# mockup.net
KiCad netlist of a schematic drawn in EAGLE
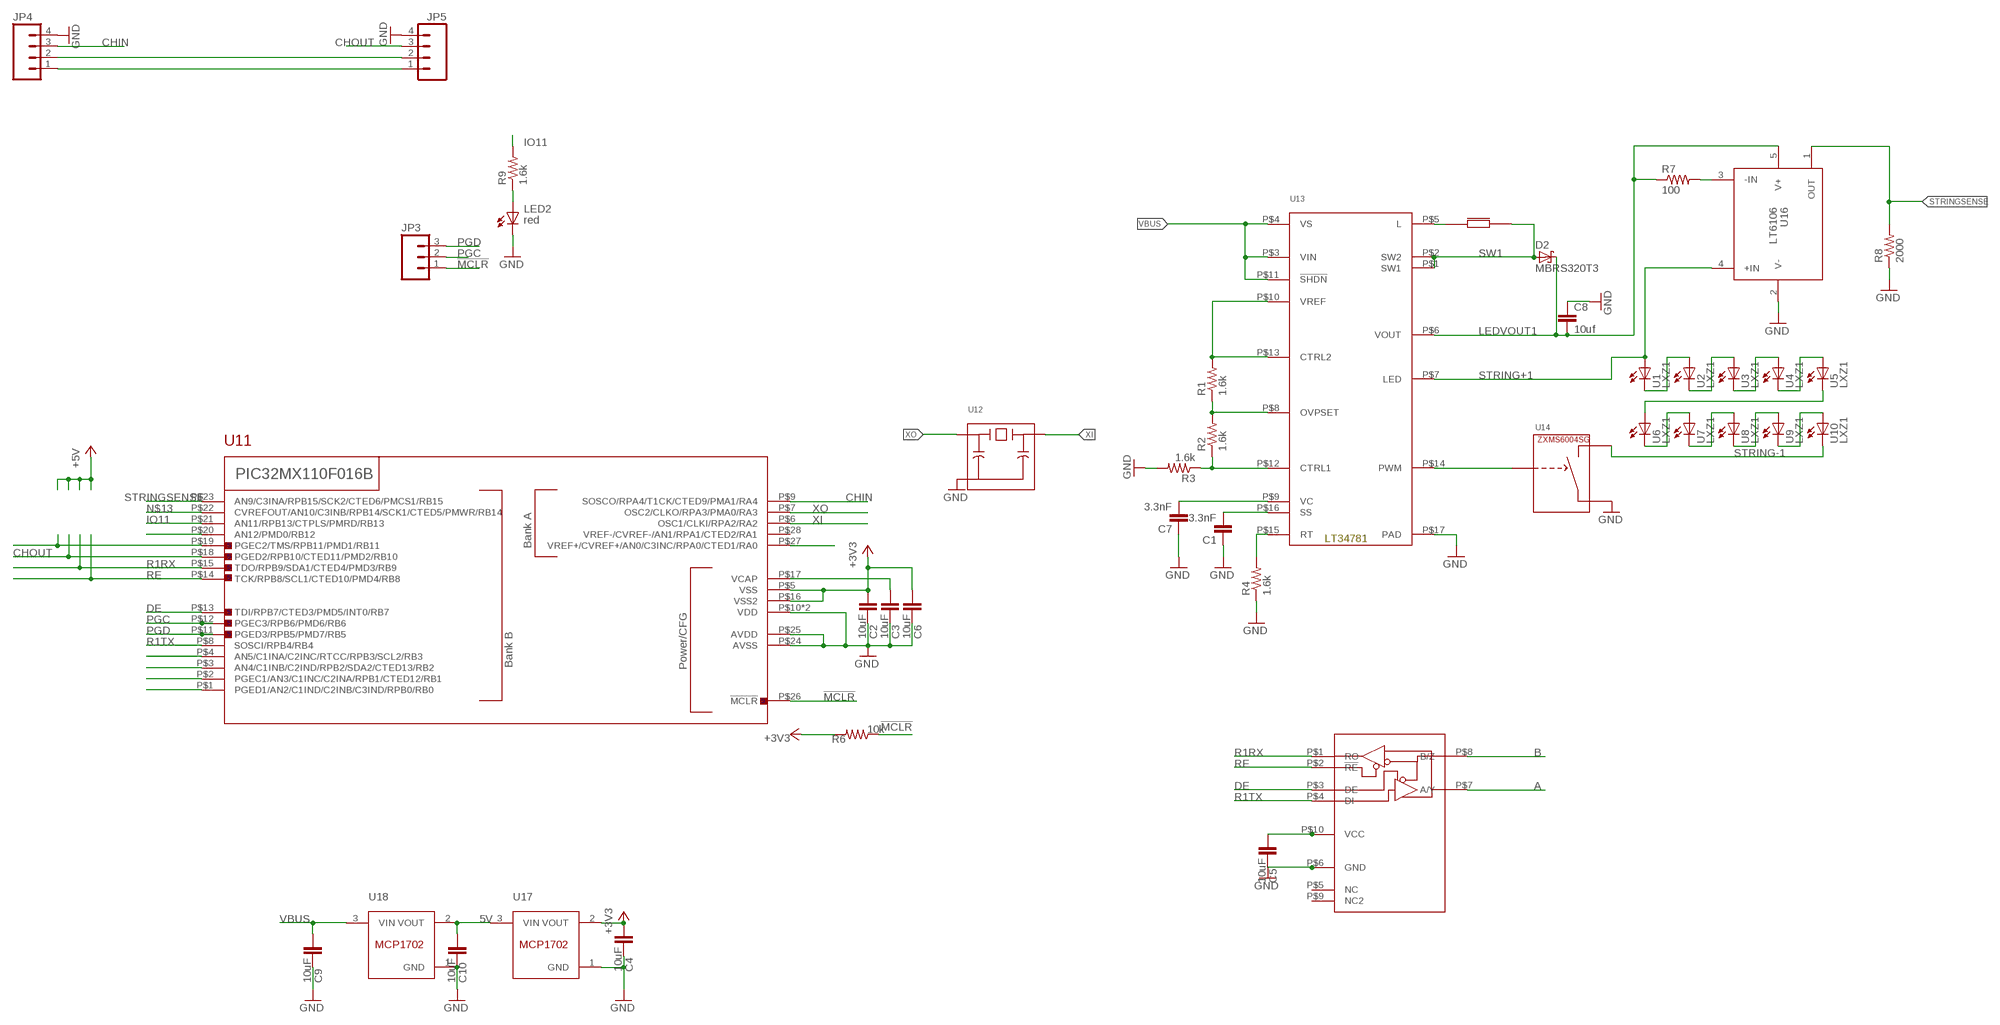
[diagram p0: schematic, sheet 1]

(export (version "E")
  (design (tool "Eeschema 10.0.6"))
  (components
    (comp (ref "C1")
      (value "3.3nF")
      (footprint "eagle-import:0402-CAP")
      (libsource (lib "eagle-import") (part "CAP0402-CAP"))
    )
    (comp (ref "C2")
      (value "10uF")
      (footprint "eagle-import:0402-CAP")
      (fields (field (name "PART#") "LMK212BJ106KG-T"))
      (libsource (lib "eagle-import") (part "SparkFun-Passives_CAP0402-CAP"))
    )
    (comp (ref "C3")
      (value "10uF")
      (footprint "eagle-import:0805")
      (fields (field (name "PART#") "LMK212BJ106KG-T"))
      (libsource (lib "eagle-import") (part "SparkFun-Passives_CAP0805"))
    )
    (comp (ref "C4")
      (value "10uF")
      (footprint "eagle-import:0402-CAP")
      (fields (field (name "PART#") "LMK212BJ106KG-T"))
      (libsource (lib "eagle-import") (part "SparkFun-Passives_CAP0402-CAP"))
    )
    (comp (ref "C5")
      (value "10uF")
      (footprint "eagle-import:0402-CAP")
      (fields (field (name "PART#") "LMK212BJ106KG-T"))
      (libsource (lib "eagle-import") (part "SparkFun-Passives_CAP0402-CAP"))
    )
    (comp (ref "C6")
      (value "10uF")
      (footprint "eagle-import:0402-CAP")
      (fields (field (name "PART#") "LMK212BJ106KG-T"))
      (libsource (lib "eagle-import") (part "SparkFun-Passives_CAP0402-CAP"))
    )
    (comp (ref "C7")
      (value "3.3nF")
      (footprint "eagle-import:0402-CAP")
      (libsource (lib "eagle-import") (part "CAP0402-CAP"))
    )
    (comp (ref "C8")
      (value "10uf")
      (footprint "eagle-import:1206")
      (libsource (lib "eagle-import") (part "CAP1206"))
    )
    (comp (ref "C9")
      (value "10uF")
      (footprint "eagle-import:0805")
      (fields (field (name "PART#") "LMK212BJ106KG-T"))
      (libsource (lib "eagle-import") (part "SparkFun-Passives_CAP0805"))
    )
    (comp (ref "C10")
      (value "10uF")
      (footprint "eagle-import:0402-CAP")
      (fields (field (name "PART#") "LMK212BJ106KG-T"))
      (libsource (lib "eagle-import") (part "SparkFun-Passives_CAP0402-CAP"))
    )
    (comp (ref "D2")
      (value "MBRS320T3")
      (footprint "eagle-import:SMC")
      (libsource (lib "eagle-import") (part "MBRS30T32"))
    )
    (comp (ref "JP3")
      (value "M031X03_NO_SILK")
      (footprint "eagle-import:1X03_NO_SILK")
      (libsource (lib "eagle-import") (part "M031X03_NO_SILK"))
    )
    (comp (ref "JP4")
      (value "M041X04_NO_SILK")
      (footprint "eagle-import:1X04_NO_SILK")
      (libsource (lib "eagle-import") (part "M041X04_NO_SILK"))
    )
    (comp (ref "JP5")
      (value "M041X04_NO_SILK")
      (footprint "eagle-import:1X04_NO_SILK")
      (libsource (lib "eagle-import") (part "M041X04_NO_SILK"))
    )
    (comp (ref "LED2")
      (value "LS L29K-G1J2-1-Z")
      (footprint "eagle-import:LED-0603")
      (libsource (lib "eagle-import") (part "LED0603"))
    )
    (comp (ref "R1")
      (value "1.6k")
      (footprint "eagle-import:0402-RES")
      (libsource (lib "eagle-import") (part "RESISTOR0402-RES"))
    )
    (comp (ref "R2")
      (value "1.6k")
      (footprint "eagle-import:0402-RES")
      (libsource (lib "eagle-import") (part "RESISTOR0402-RES"))
    )
    (comp (ref "R3")
      (value "1.6k")
      (footprint "eagle-import:0402-RES")
      (libsource (lib "eagle-import") (part "RESISTOR0402-RES"))
    )
    (comp (ref "R4")
      (value "1.6k")
      (footprint "eagle-import:0402-RES")
      (libsource (lib "eagle-import") (part "RESISTOR0402-RES"))
    )
    (comp (ref "R6")
      (value "10k")
      (footprint "eagle-import:0402-RES")
      (libsource (lib "eagle-import") (part "RESISTOR0402-RES"))
    )
    (comp (ref "R7")
      (value "100")
      (footprint "eagle-import:0402-RES")
      (libsource (lib "eagle-import") (part "RESISTOR0402-RES"))
    )
    (comp (ref "R8")
      (value "2000")
      (footprint "eagle-import:0402-RES")
      (libsource (lib "eagle-import") (part "RESISTOR0402-RES"))
    )
    (comp (ref "R9")
      (value "1.6k")
      (footprint "eagle-import:0402-RES")
      (libsource (lib "eagle-import") (part "RESISTOR0402-RES"))
    )
    (comp (ref "U$27")
      (value "74404064068")
      (footprint "eagle-import:74404064068")
      (libsource (lib "eagle-import") (part "74404064068"))
    )
    (comp (ref "U1")
      (value "LXZ1")
      (footprint "eagle-import:LXZ1")
      (libsource (lib "eagle-import") (part "LXZ1"))
    )
    (comp (ref "U2")
      (value "LXZ1")
      (footprint "eagle-import:LXZ1")
      (libsource (lib "eagle-import") (part "LXZ1"))
    )
    (comp (ref "U3")
      (value "LXZ1")
      (footprint "eagle-import:LXZ1")
      (libsource (lib "eagle-import") (part "LXZ1"))
    )
    (comp (ref "U4")
      (value "LXZ1")
      (footprint "eagle-import:LXZ1")
      (libsource (lib "eagle-import") (part "LXZ1"))
    )
    (comp (ref "U5")
      (value "LXZ1")
      (footprint "eagle-import:LXZ1")
      (libsource (lib "eagle-import") (part "LXZ1"))
    )
    (comp (ref "U6")
      (value "LXZ1")
      (footprint "eagle-import:LXZ1")
      (libsource (lib "eagle-import") (part "LXZ1"))
    )
    (comp (ref "U7")
      (value "LXZ1")
      (footprint "eagle-import:LXZ1")
      (libsource (lib "eagle-import") (part "LXZ1"))
    )
    (comp (ref "U8")
      (value "LXZ1")
      (footprint "eagle-import:LXZ1")
      (libsource (lib "eagle-import") (part "LXZ1"))
    )
    (comp (ref "U9")
      (value "LXZ1")
      (footprint "eagle-import:LXZ1")
      (libsource (lib "eagle-import") (part "LXZ1"))
    )
    (comp (ref "U10")
      (value "LXZ1")
      (footprint "eagle-import:LXZ1")
      (libsource (lib "eagle-import") (part "LXZ1"))
    )
    (comp (ref "U11")
      (value "PIC32MX110QFN")
      (footprint "eagle-import:28-QFN")
      (libsource (lib "eagle-import") (part "PIC32MX110QFN"))
    )
    (comp (ref "U12")
      (value "CSTCE")
      (footprint "eagle-import:CSTCE")
      (libsource (lib "eagle-import") (part "CSTCE"))
    )
    (comp (ref "U13")
      (value "34781F")
      (footprint "eagle-import:TSSOP16")
      (libsource (lib "eagle-import") (part "34781F"))
    )
    (comp (ref "U14")
      (value "ZXMS6004SG")
      (footprint "eagle-import:SOT223")
      (libsource (lib "eagle-import") (part "ZXMS6004SG"))
    )
    (comp (ref "U15")
      (value "ISL3159E")
      (footprint "eagle-import:DFN10")
      (libsource (lib "eagle-import") (part "ISL3159E"))
    )
    (comp (ref "U16")
      (value "LT6106")
      (footprint "eagle-import:5-LEAD-TSOT-23")
      (libsource (lib "eagle-import") (part "LT6106"))
    )
    (comp (ref "U17")
      (value "MCP1702T")
      (footprint "eagle-import:SOT23")
      (libsource (lib "eagle-import") (part "MCP1702T"))
    )
    (comp (ref "U18")
      (value "MCP1702T")
      (footprint "eagle-import:SOT23")
      (libsource (lib "eagle-import") (part "MCP1702T"))
    )
  )
  (nets
    (net (code "1") (name "+3V3") (class "Default")
      (node (ref "C2") (pin "1") (pinfunction "1_1") (pintype "passive"))
      (node (ref "C4") (pin "1") (pinfunction "1_1") (pintype "passive"))
      (node (ref "C6") (pin "1") (pinfunction "1_1") (pintype "passive"))
      (node (ref "R6") (pin "2") (pinfunction "2_2") (pintype "passive"))
      (node (ref "U11") (pin "P$16") (pinfunction "VSS2_P$16") (pintype "bidirectional"))
      (node (ref "U11") (pin "P$5") (pinfunction "VSS_P$5") (pintype "bidirectional"))
      (node (ref "U17") (pin "2") (pinfunction "VOUT_2") (pintype "bidirectional"))
    )
    (net (code "3") (name "/5V") (class "Default")
      (node (ref "C10") (pin "1") (pinfunction "1_1") (pintype "passive"))
      (node (ref "C5") (pin "1") (pinfunction "1_1") (pintype "passive"))
      (node (ref "U15") (pin "P$10") (pinfunction "VCC_P$10") (pintype "bidirectional"))
      (node (ref "U17") (pin "3") (pinfunction "VIN_3") (pintype "bidirectional"))
      (node (ref "U18") (pin "2") (pinfunction "VOUT_2") (pintype "bidirectional"))
    )
    (net (code "4") (name "/A") (class "Default")
      (node (ref "JP4") (pin "1") (pinfunction "1_1") (pintype "passive"))
      (node (ref "JP5") (pin "1") (pinfunction "1_1") (pintype "passive"))
      (node (ref "U15") (pin "P$7") (pinfunction "A/Y_P$7") (pintype "bidirectional"))
    )
    (net (code "5") (name "/B") (class "Default")
      (node (ref "JP4") (pin "2") (pinfunction "2_2") (pintype "passive"))
      (node (ref "JP5") (pin "2") (pinfunction "2_2") (pintype "passive"))
      (node (ref "U15") (pin "P$8") (pinfunction "B/Z_P$8") (pintype "bidirectional"))
    )
    (net (code "6") (name "/CHIN") (class "Default")
      (node (ref "JP4") (pin "3") (pinfunction "3_3") (pintype "passive"))
      (node (ref "U11") (pin "P$9") (pinfunction "SOSCO/RPA4/T1CK/CTED9/PMA1/RA4_P$9") (pintype "bidirectional"))
    )
    (net (code "7") (name "/CHOUT") (class "Default")
      (node (ref "JP5") (pin "3") (pinfunction "3_3") (pintype "passive"))
      (node (ref "U11") (pin "P$18") (pinfunction "PGED2/RPB10/CTED11/PMD2/RB10_P$18") (pintype "bidirectional"))
    )
    (net (code "8") (name "/DE") (class "Default")
      (node (ref "U11") (pin "P$13") (pinfunction "TDI/RPB7/CTED3/PMD5/INT0/RB7_P$13") (pintype "bidirectional"))
      (node (ref "U15") (pin "P$3") (pinfunction "DE_P$3") (pintype "bidirectional"))
    )
    (net (code "9") (name "/IO11") (class "Default")
      (node (ref "R9") (pin "2") (pinfunction "2_2") (pintype "passive"))
      (node (ref "U11") (pin "P$21") (pinfunction "AN11/RPB13/CTPLS/PMRD/RB13_P$21") (pintype "bidirectional"))
    )
    (net (code "10") (name "/LEDVOUT1") (class "Default")
      (node (ref "C8") (pin "2") (pinfunction "2_2") (pintype "passive"))
      (node (ref "D2") (pin "C") (pinfunction "C_C") (pintype "passive"))
      (node (ref "R7") (pin "1") (pinfunction "1_1") (pintype "passive"))
      (node (ref "U13") (pin "P$6") (pinfunction "VOUT_P$6") (pintype "bidirectional"))
      (node (ref "U16") (pin "5") (pinfunction "V+_5") (pintype "power_in"))
    )
    (net (code "11") (name "/N$13") (class "Default")
      (node (ref "U11") (pin "P$22") (pinfunction "CVREFOUT/AN10/C3INB/RPB14/SCK1/CTED5/PMWR/RB14_P$22") (pintype "bidirectional"))
      (node (ref "U13") (pin "P$14") (pinfunction "PWM_P$14") (pintype "bidirectional"))
      (node (ref "U14") (pin "1") (pinfunction "IN_1") (pintype "bidirectional"))
    )
    (net (code "12") (name "/PGC") (class "Default")
      (node (ref "JP3") (pin "2") (pinfunction "2_2") (pintype "passive"))
      (node (ref "U11") (pin "P$12") (pinfunction "PGEC3/RPB6/PMD6/RB6_P$12") (pintype "bidirectional"))
    )
    (net (code "13") (name "/PGD") (class "Default")
      (node (ref "JP3") (pin "3") (pinfunction "3_3") (pintype "passive"))
      (node (ref "U11") (pin "P$11") (pinfunction "PGED3/RPB5/PMD7/RB5_P$11") (pintype "bidirectional"))
    )
    (net (code "14") (name "/R1RX") (class "Default")
      (node (ref "U11") (pin "P$15") (pinfunction "TDO/RPB9/SDA1/CTED4/PMD3/RB9_P$15") (pintype "bidirectional"))
      (node (ref "U15") (pin "P$1") (pinfunction "RO_P$1") (pintype "bidirectional"))
    )
    (net (code "15") (name "/R1TX") (class "Default")
      (node (ref "U11") (pin "P$8") (pinfunction "SOSCI/RPB4/RB4_P$8") (pintype "bidirectional"))
      (node (ref "U15") (pin "P$4") (pinfunction "DI_P$4") (pintype "bidirectional"))
    )
    (net (code "16") (name "/RE") (class "Default")
      (node (ref "U11") (pin "P$14") (pinfunction "TCK/RPB8/SCL1/CTED10/PMD4/RB8_P$14") (pintype "bidirectional"))
      (node (ref "U15") (pin "P$2") (pinfunction "~{RE}_P$2") (pintype "bidirectional"))
    )
    (net (code "17") (name "/STRING+1") (class "Default")
      (node (ref "U1") (pin "A") (pinfunction "A_A") (pintype "passive"))
      (node (ref "U13") (pin "P$7") (pinfunction "LED_P$7") (pintype "bidirectional"))
      (node (ref "U16") (pin "4") (pinfunction "+IN_4") (pintype "input"))
    )
    (net (code "18") (name "/STRING-1") (class "Default")
      (node (ref "U10") (pin "K") (pinfunction "C_K") (pintype "passive"))
      (node (ref "U14") (pin "2") (pinfunction "D_2") (pintype "bidirectional"))
    )
    (net (code "19") (name "/SW1") (class "Default")
      (node (ref "D2") (pin "A") (pinfunction "A_A") (pintype "passive"))
      (node (ref "U$27") (pin "P$2") (pinfunction "P$2_P$2") (pintype "bidirectional"))
      (node (ref "U13") (pin "P$1") (pinfunction "SW1_P$1") (pintype "bidirectional"))
      (node (ref "U13") (pin "P$2") (pinfunction "SW2_P$2") (pintype "bidirectional"))
    )
    (net (code "20") (name "/~{MCLR}") (class "Default")
      (node (ref "JP3") (pin "1") (pinfunction "1_1") (pintype "passive"))
      (node (ref "R6") (pin "1") (pinfunction "1_1") (pintype "passive"))
      (node (ref "U11") (pin "P$26") (pinfunction "~{MCLR}_P$26") (pintype "bidirectional"))
    )
    (net (code "21") (name "GND") (class "Default")
      (node (ref "C1") (pin "1") (pinfunction "1_1") (pintype "passive"))
      (node (ref "C10") (pin "2") (pinfunction "2_2") (pintype "passive"))
      (node (ref "C2") (pin "2") (pinfunction "2_2") (pintype "passive"))
      (node (ref "C3") (pin "2") (pinfunction "2_2") (pintype "passive"))
      (node (ref "C4") (pin "2") (pinfunction "2_2") (pintype "passive"))
      (node (ref "C5") (pin "2") (pinfunction "2_2") (pintype "passive"))
      (node (ref "C6") (pin "2") (pinfunction "2_2") (pintype "passive"))
      (node (ref "C7") (pin "1") (pinfunction "1_1") (pintype "passive"))
      (node (ref "C8") (pin "1") (pinfunction "1_1") (pintype "passive"))
      (node (ref "C9") (pin "2") (pinfunction "2_2") (pintype "passive"))
      (node (ref "JP4") (pin "4") (pinfunction "4_4") (pintype "passive"))
      (node (ref "JP5") (pin "4") (pinfunction "4_4") (pintype "passive"))
      (node (ref "LED2") (pin "C") (pinfunction "C_C") (pintype "passive"))
      (node (ref "R3") (pin "2") (pinfunction "2_2") (pintype "passive"))
      (node (ref "R4") (pin "1") (pinfunction "1_1") (pintype "passive"))
      (node (ref "R8") (pin "1") (pinfunction "1_1") (pintype "passive"))
      (node (ref "U11") (pin "P$10") (pinfunction "VDD_P$10") (pintype "bidirectional"))
      (node (ref "U11") (pin "P$24") (pinfunction "AVSS_P$24") (pintype "bidirectional"))
      (node (ref "U11") (pin "P$25") (pinfunction "AVDD_P$25") (pintype "bidirectional"))
      (node (ref "U11") (pin "P$29") (pinfunction "VDD_P$29") (pintype "bidirectional"))
      (node (ref "U12") (pin "2") (pinfunction "2_2") (pintype "bidirectional"))
      (node (ref "U13") (pin "P$17") (pinfunction "PAD_P$17") (pintype "bidirectional"))
      (node (ref "U14") (pin "3") (pinfunction "S_3") (pintype "bidirectional"))
      (node (ref "U14") (pin "4") (pinfunction "S_4") (pintype "bidirectional"))
      (node (ref "U15") (pin "P$6") (pinfunction "GND_P$6") (pintype "bidirectional"))
      (node (ref "U16") (pin "2") (pinfunction "V-_2") (pintype "power_in"))
      (node (ref "U17") (pin "1") (pinfunction "GND_1") (pintype "bidirectional"))
      (node (ref "U18") (pin "1") (pinfunction "GND_1") (pintype "bidirectional"))
    )
    (net (code "22") (name "Net-(LED2-PadA)") (class "Default")
      (node (ref "LED2") (pin "A") (pinfunction "A_A") (pintype "passive"))
      (node (ref "R9") (pin "1") (pinfunction "1_1") (pintype "passive"))
    )
    (net (code "23") (name "Net-(U1-C)") (class "Default")
      (node (ref "U1") (pin "K") (pinfunction "C_K") (pintype "passive"))
      (node (ref "U2") (pin "A") (pinfunction "A_A") (pintype "passive"))
    )
    (net (code "24") (name "Net-(U2-C)") (class "Default")
      (node (ref "U2") (pin "K") (pinfunction "C_K") (pintype "passive"))
      (node (ref "U3") (pin "A") (pinfunction "A_A") (pintype "passive"))
    )
    (net (code "25") (name "Net-(U3-C)") (class "Default")
      (node (ref "U3") (pin "K") (pinfunction "C_K") (pintype "passive"))
      (node (ref "U4") (pin "A") (pinfunction "A_A") (pintype "passive"))
    )
    (net (code "26") (name "Net-(U4-C)") (class "Default")
      (node (ref "U4") (pin "K") (pinfunction "C_K") (pintype "passive"))
      (node (ref "U5") (pin "A") (pinfunction "A_A") (pintype "passive"))
    )
    (net (code "27") (name "Net-(U5-C)") (class "Default")
      (node (ref "U5") (pin "K") (pinfunction "C_K") (pintype "passive"))
      (node (ref "U6") (pin "A") (pinfunction "A_A") (pintype "passive"))
    )
    (net (code "28") (name "Net-(U6-C)") (class "Default")
      (node (ref "U6") (pin "K") (pinfunction "C_K") (pintype "passive"))
      (node (ref "U7") (pin "A") (pinfunction "A_A") (pintype "passive"))
    )
    (net (code "29") (name "Net-(U7-C)") (class "Default")
      (node (ref "U7") (pin "K") (pinfunction "C_K") (pintype "passive"))
      (node (ref "U8") (pin "A") (pinfunction "A_A") (pintype "passive"))
    )
    (net (code "30") (name "Net-(U8-C)") (class "Default")
      (node (ref "U8") (pin "K") (pinfunction "C_K") (pintype "passive"))
      (node (ref "U9") (pin "A") (pinfunction "A_A") (pintype "passive"))
    )
    (net (code "31") (name "Net-(U9-C)") (class "Default")
      (node (ref "U10") (pin "A") (pinfunction "A_A") (pintype "passive"))
      (node (ref "U9") (pin "K") (pinfunction "C_K") (pintype "passive"))
    )
    (net (code "32") (name "Net-(U11-VCAP)") (class "Default")
      (node (ref "C3") (pin "1") (pinfunction "1_1") (pintype "passive"))
      (node (ref "U11") (pin "P$17") (pinfunction "VCAP_P$17") (pintype "bidirectional"))
    )
    (net (code "33") (name "Net-(U13-CTRL1)") (class "Default")
      (node (ref "R2") (pin "1") (pinfunction "1_1") (pintype "passive"))
      (node (ref "R3") (pin "1") (pinfunction "1_1") (pintype "passive"))
      (node (ref "U13") (pin "P$12") (pinfunction "CTRL1_P$12") (pintype "bidirectional"))
    )
    (net (code "34") (name "Net-(U13-CTRL2)") (class "Default")
      (node (ref "R1") (pin "2") (pinfunction "2_2") (pintype "passive"))
      (node (ref "U13") (pin "P$10") (pinfunction "VREF_P$10") (pintype "bidirectional"))
      (node (ref "U13") (pin "P$13") (pinfunction "CTRL2_P$13") (pintype "bidirectional"))
    )
    (net (code "35") (name "Net-(U13-L)") (class "Default")
      (node (ref "U$27") (pin "P$1") (pinfunction "P$1_P$1") (pintype "bidirectional"))
      (node (ref "U13") (pin "P$5") (pinfunction "L_P$5") (pintype "bidirectional"))
    )
    (net (code "36") (name "Net-(U13-OVPSET)") (class "Default")
      (node (ref "R1") (pin "1") (pinfunction "1_1") (pintype "passive"))
      (node (ref "R2") (pin "2") (pinfunction "2_2") (pintype "passive"))
      (node (ref "U13") (pin "P$8") (pinfunction "OVPSET_P$8") (pintype "bidirectional"))
    )
    (net (code "37") (name "Net-(U13-RT)") (class "Default")
      (node (ref "R4") (pin "2") (pinfunction "2_2") (pintype "passive"))
      (node (ref "U13") (pin "P$15") (pinfunction "RT_P$15") (pintype "bidirectional"))
    )
    (net (code "38") (name "Net-(U13-SS)") (class "Default")
      (node (ref "C1") (pin "2") (pinfunction "2_2") (pintype "passive"))
      (node (ref "U13") (pin "P$16") (pinfunction "SS_P$16") (pintype "bidirectional"))
    )
    (net (code "39") (name "Net-(U13-VC)") (class "Default")
      (node (ref "C7") (pin "2") (pinfunction "2_2") (pintype "passive"))
      (node (ref "U13") (pin "P$9") (pinfunction "VC_P$9") (pintype "bidirectional"))
    )
    (net (code "40") (name "Net-(U16--IN)") (class "Default")
      (node (ref "R7") (pin "2") (pinfunction "2_2") (pintype "passive"))
      (node (ref "U16") (pin "3") (pinfunction "-IN_3") (pintype "input"))
    )
    (net (code "41") (name "STRINGSENSE") (class "Default")
      (node (ref "R8") (pin "2") (pinfunction "2_2") (pintype "passive"))
      (node (ref "U11") (pin "P$23") (pinfunction "AN9/C3INA/RPB15/SCK2/CTED6/PMCS1/RB15_P$23") (pintype "bidirectional"))
      (node (ref "U16") (pin "1") (pinfunction "OUT_1") (pintype "output"))
    )
    (net (code "42") (name "VBUS") (class "Default")
      (node (ref "C9") (pin "1") (pinfunction "1_1") (pintype "passive"))
      (node (ref "U13") (pin "P$11") (pinfunction "~{SHDN}_P$11") (pintype "bidirectional"))
      (node (ref "U13") (pin "P$3") (pinfunction "VIN_P$3") (pintype "bidirectional"))
      (node (ref "U13") (pin "P$4") (pinfunction "VS_P$4") (pintype "bidirectional"))
      (node (ref "U18") (pin "3") (pinfunction "VIN_3") (pintype "bidirectional"))
    )
    (net (code "43") (name "XI") (class "Default")
      (node (ref "U11") (pin "P$6") (pinfunction "OSC1/CLKI/RPA2/RA2_P$6") (pintype "bidirectional"))
      (node (ref "U12") (pin "3") (pinfunction "3_3") (pintype "bidirectional"))
    )
    (net (code "44") (name "XO") (class "Default")
      (node (ref "U11") (pin "P$7") (pinfunction "OSC2/CLKO/RPA3/PMA0/RA3_P$7") (pintype "bidirectional"))
      (node (ref "U12") (pin "1") (pinfunction "1_1") (pintype "bidirectional"))
    )
    (net (code "45") (name "unconnected-(U11-AN4{slash}C1INB{slash}C2IND{slash}RPB2{slash}SDA2{slash}CTED13{slash}RB2-PadP$3)") (class "Default")
      (node (ref "U11") (pin "P$3") (pinfunction "AN4/C1INB/C2IND/RPB2/SDA2/CTED13/RB2_P$3") (pintype "bidirectional"))
    )
    (net (code "46") (name "unconnected-(U11-AN5{slash}C1INA{slash}C2INC{slash}RTCC{slash}RPB3{slash}SCL2{slash}RB3-PadP$4)") (class "Default")
      (node (ref "U11") (pin "P$4") (pinfunction "AN5/C1INA/C2INC/RTCC/RPB3/SCL2/RB3_P$4") (pintype "bidirectional"))
    )
    (net (code "47") (name "unconnected-(U11-AN12{slash}PMD0{slash}RB12-PadP$20)") (class "Default")
      (node (ref "U11") (pin "P$20") (pinfunction "AN12/PMD0/RB12_P$20") (pintype "bidirectional"))
    )
    (net (code "48") (name "unconnected-(U11-PGEC1{slash}AN3{slash}C1INC{slash}C2INA{slash}RPB1{slash}CTED12{slash}RB1-PadP$2)") (class "Default")
      (node (ref "U11") (pin "P$2") (pinfunction "PGEC1/AN3/C1INC/C2INA/RPB1/CTED12/RB1_P$2") (pintype "bidirectional"))
    )
    (net (code "49") (name "unconnected-(U11-PGEC2{slash}TMS{slash}RPB11{slash}PMD1{slash}RB11-PadP$19)") (class "Default")
      (node (ref "U11") (pin "P$19") (pinfunction "PGEC2/TMS/RPB11/PMD1/RB11_P$19") (pintype "bidirectional"))
    )
    (net (code "50") (name "unconnected-(U11-PGED1{slash}AN2{slash}C1IND{slash}C2INB{slash}C3IND{slash}RPB0{slash}RB0-PadP$1)") (class "Default")
      (node (ref "U11") (pin "P$1") (pinfunction "PGED1/AN2/C1IND/C2INB/C3IND/RPB0/RB0_P$1") (pintype "bidirectional"))
    )
    (net (code "51") (name "unconnected-(U11-VREF+{slash}CVREF+{slash}AN0{slash}C3INC{slash}RPA0{slash}CTED1{slash}RA0-PadP$27)") (class "Default")
      (node (ref "U11") (pin "P$27") (pinfunction "VREF+/CVREF+/AN0/C3INC/RPA0/CTED1/RA0_P$27") (pintype "bidirectional"))
    )
    (net (code "52") (name "unconnected-(U11-VREF-{slash}CVREF-{slash}AN1{slash}RPA1{slash}CTED2{slash}RA1-PadP$28)") (class "Default")
      (node (ref "U11") (pin "P$28") (pinfunction "VREF-/CVREF-/AN1/RPA1/CTED2/RA1_P$28") (pintype "bidirectional"))
    )
    (net (code "53") (name "unconnected-(U15-NC-PadP$5)") (class "Default")
      (node (ref "U15") (pin "P$5") (pinfunction "NC_P$5") (pintype "bidirectional"))
    )
    (net (code "54") (name "unconnected-(U15-NC2-PadP$9)") (class "Default")
      (node (ref "U15") (pin "P$9") (pinfunction "NC2_P$9") (pintype "bidirectional"))
    )
  )
)
